# design.net
KiCad netlist of a schematic drawn in Altium Designer
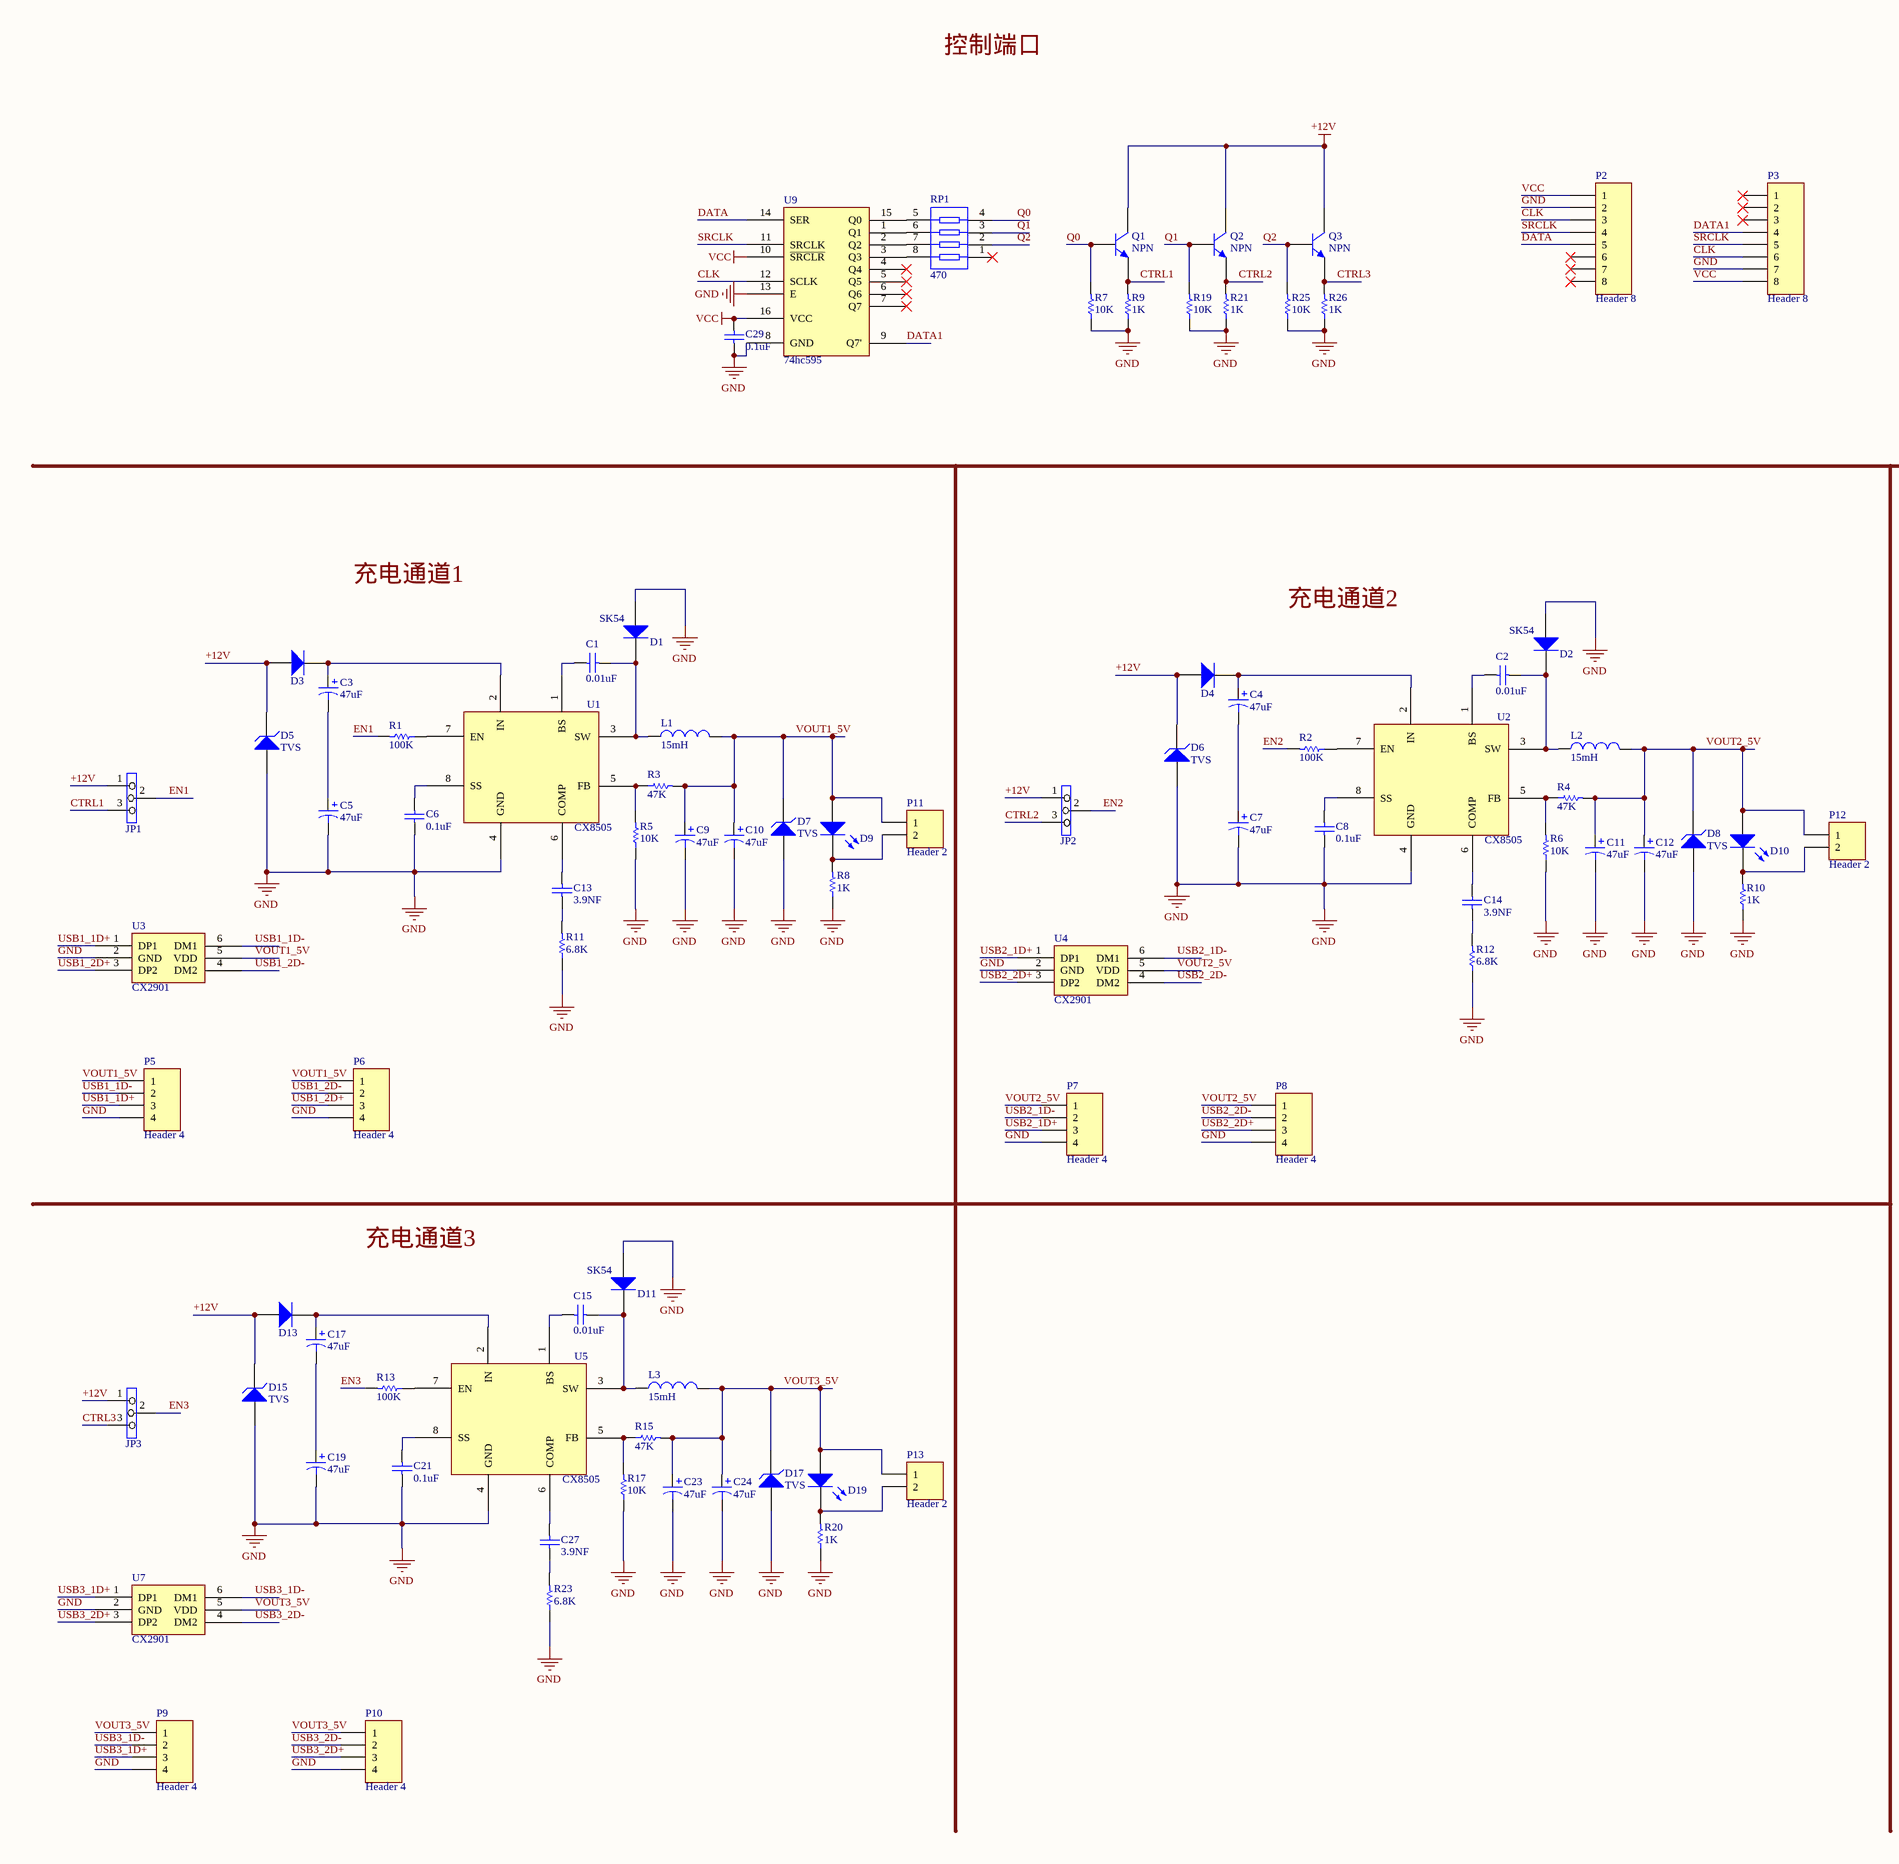
[diagram p0: 充电.SchDoc, left]
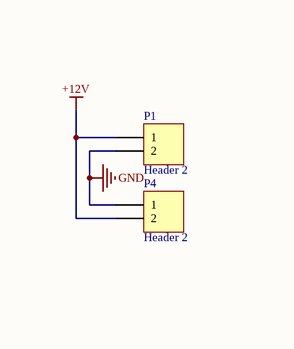
[diagram p1: 充电.SchDoc, right]

(export (version "E")
  (design (tool "Eeschema 10.0.6"))
  (components
    (comp (ref "C1")
      (value "0.01uF")
      (footprint "CAPC2012M")
      (description "Capacitor")
      (fields (field (name "PUBLISHER") "Altium Limited"))
      (libsource (lib "device") (part "Cap"))
    )
    (comp (ref "C2")
      (value "0.01uF")
      (footprint "CAPC2012M")
      (description "Capacitor")
      (fields (field (name "PUBLISHER") "Altium Limited"))
      (libsource (lib "device") (part "Cap"))
    )
    (comp (ref "C3")
      (value "47uF")
      (footprint "CAPPR2-5x11.5")
      (description "Polarized Capacitor (22uf-47uf)")
      (fields (field (name "PUBLISHER") "Altium Limited"))
      (libsource (lib "device") (part "Cap Pol2"))
    )
    (comp (ref "C4")
      (value "47uF")
      (footprint "CAPPR2-5x11.5")
      (description "Polarized Capacitor (22uf-47uf)")
      (fields (field (name "PUBLISHER") "Altium Limited"))
      (libsource (lib "device") (part "Cap Pol2"))
    )
    (comp (ref "C5")
      (value "47uF")
      (footprint "CAPPR2-5x11.5")
      (description "Polarized Capacitor (22uf-47uf)")
      (fields (field (name "PUBLISHER") "Altium Limited"))
      (libsource (lib "device") (part "Cap Pol2"))
    )
    (comp (ref "C6")
      (value "0.1uF")
      (footprint "CAPC2012M")
      (description "Capacitor")
      (fields (field (name "PUBLISHER") "Altium Limited"))
      (libsource (lib "device") (part "Cap"))
    )
    (comp (ref "C7")
      (value "47uF")
      (footprint "CAPPR2-5x11.5")
      (description "Polarized Capacitor (22uf-47uf)")
      (fields (field (name "PUBLISHER") "Altium Limited"))
      (libsource (lib "device") (part "Cap Pol2"))
    )
    (comp (ref "C8")
      (value "0.1uF")
      (footprint "CAPC2012M")
      (description "Capacitor")
      (fields (field (name "PUBLISHER") "Altium Limited"))
      (libsource (lib "device") (part "Cap"))
    )
    (comp (ref "C9")
      (value "47uF")
      (footprint "CAPPR2-5x11.5")
      (description "Polarized Capacitor (22uf-47uf)")
      (fields (field (name "PUBLISHER") "Altium Limited"))
      (libsource (lib "device") (part "Cap Pol2"))
    )
    (comp (ref "C10")
      (value "47uF")
      (footprint "CAPPR2-5x11.5")
      (description "Polarized Capacitor (22uf-47uf)")
      (fields (field (name "PUBLISHER") "Altium Limited"))
      (libsource (lib "device") (part "Cap Pol2"))
    )
    (comp (ref "C11")
      (value "47uF")
      (footprint "CAPPR2-5x11.5")
      (description "Polarized Capacitor (22uf-47uf)")
      (fields (field (name "PUBLISHER") "Altium Limited"))
      (libsource (lib "device") (part "Cap Pol2"))
    )
    (comp (ref "C12")
      (value "47uF")
      (footprint "CAPPR2-5x11.5")
      (description "Polarized Capacitor (22uf-47uf)")
      (fields (field (name "PUBLISHER") "Altium Limited"))
      (libsource (lib "device") (part "Cap Pol2"))
    )
    (comp (ref "C13")
      (value "3.9NF")
      (footprint "CAPC2012M")
      (description "Capacitor")
      (fields (field (name "PUBLISHER") "Altium Limited"))
      (libsource (lib "device") (part "Cap"))
    )
    (comp (ref "C14")
      (value "3.9NF")
      (footprint "CAPC2012M")
      (description "Capacitor")
      (fields (field (name "PUBLISHER") "Altium Limited"))
      (libsource (lib "device") (part "Cap"))
    )
    (comp (ref "C15")
      (value "0.01uF")
      (footprint "CAPC2012M")
      (description "Capacitor")
      (fields (field (name "PUBLISHER") "Altium Limited"))
      (libsource (lib "device") (part "Cap"))
    )
    (comp (ref "C17")
      (value "47uF")
      (footprint "CAPPR2-5x11.5")
      (description "Polarized Capacitor (22uf-47uf)")
      (fields (field (name "PUBLISHER") "Altium Limited"))
      (libsource (lib "device") (part "Cap Pol2"))
    )
    (comp (ref "C19")
      (value "47uF")
      (footprint "CAPPR2-5x11.5")
      (description "Polarized Capacitor (22uf-47uf)")
      (fields (field (name "PUBLISHER") "Altium Limited"))
      (libsource (lib "device") (part "Cap Pol2"))
    )
    (comp (ref "C21")
      (value "0.1uF")
      (footprint "CAPC2012M")
      (description "Capacitor")
      (fields (field (name "PUBLISHER") "Altium Limited"))
      (libsource (lib "device") (part "Cap"))
    )
    (comp (ref "C23")
      (value "47uF")
      (footprint "CAPPR2-5x11.5")
      (description "Polarized Capacitor (22uf-47uf)")
      (fields (field (name "PUBLISHER") "Altium Limited"))
      (libsource (lib "device") (part "Cap Pol2"))
    )
    (comp (ref "C24")
      (value "47uF")
      (footprint "CAPPR2-5x11.5")
      (description "Polarized Capacitor (22uf-47uf)")
      (fields (field (name "PUBLISHER") "Altium Limited"))
      (libsource (lib "device") (part "Cap Pol2"))
    )
    (comp (ref "C27")
      (value "3.9NF")
      (footprint "CAPC2012M")
      (description "Capacitor")
      (fields (field (name "PUBLISHER") "Altium Limited"))
      (libsource (lib "device") (part "Cap"))
    )
    (comp (ref "C29")
      (value "0.1uF")
      (footprint "CAPC2012M")
      (description "Capacitor")
      (fields (field (name "PUBLISHER") "Altium Limited"))
      (libsource (lib "device") (part "Cap"))
    )
    (comp (ref "D1")
      (value "SK54")
      (footprint "SMC")
      (description "Default Diode")
      (fields (field (name "PUBLISHER") "Altium Limited"))
      (libsource (lib "") (part "Diode_1"))
    )
    (comp (ref "D2")
      (value "SK54")
      (footprint "SMC")
      (description "Default Diode")
      (fields (field (name "PUBLISHER") "Altium Limited"))
      (libsource (lib "") (part "Diode_1"))
    )
    (comp (ref "D3")
      (value "1N4007")
      (footprint "DSO-C2/X1.8")
      (description "Default Diode")
      (fields (field (name "PUBLISHER") "Altium Limited"))
      (libsource (lib "device") (part "Diode"))
    )
    (comp (ref "D4")
      (value "1N4007")
      (footprint "DSO-C2/X1.8")
      (description "Default Diode")
      (fields (field (name "PUBLISHER") "Altium Limited"))
      (libsource (lib "device") (part "Diode"))
    )
    (comp (ref "D5")
      (value "TVS")
      (footprint "SMB")
      (description "TVS瞬态抑制二极管")
      (fields (field (name "PUBLISHER") "Altium Limited"))
      (libsource (lib "device") (part "TVS"))
    )
    (comp (ref "D6")
      (value "TVS")
      (footprint "SMB")
      (description "TVS瞬态抑制二极管")
      (fields (field (name "PUBLISHER") "Altium Limited"))
      (libsource (lib "device") (part "TVS"))
    )
    (comp (ref "D7")
      (value "TVS")
      (footprint "DSO-C2/X1.8")
      (description "TVS瞬态抑制二极管")
      (fields (field (name "PUBLISHER") "Altium Limited"))
      (libsource (lib "device") (part "TVS"))
    )
    (comp (ref "D8")
      (value "TVS")
      (footprint "DSO-C2/X1.8")
      (description "TVS瞬态抑制二极管")
      (fields (field (name "PUBLISHER") "Altium Limited"))
      (libsource (lib "device") (part "TVS"))
    )
    (comp (ref "D9")
      (value "LED")
      (footprint "LED")
      (description "Typical INFRARED GaAs LED")
      (fields (field (name "PUBLISHER") "Altium Limited"))
      (libsource (lib "device") (part "LED"))
    )
    (comp (ref "D10")
      (value "LED")
      (footprint "LED")
      (description "Typical INFRARED GaAs LED")
      (fields (field (name "PUBLISHER") "Altium Limited"))
      (libsource (lib "device") (part "LED"))
    )
    (comp (ref "D11")
      (value "SK54")
      (footprint "SMC")
      (description "Default Diode")
      (fields (field (name "PUBLISHER") "Altium Limited"))
      (libsource (lib "") (part "Diode_1"))
    )
    (comp (ref "D13")
      (value "1N4007")
      (footprint "DSO-C2/X1.8")
      (description "Default Diode")
      (fields (field (name "PUBLISHER") "Altium Limited"))
      (libsource (lib "device") (part "Diode"))
    )
    (comp (ref "D15")
      (value "TVS")
      (footprint "SMB")
      (description "TVS瞬态抑制二极管")
      (fields (field (name "PUBLISHER") "Altium Limited"))
      (libsource (lib "device") (part "TVS"))
    )
    (comp (ref "D17")
      (value "TVS")
      (footprint "DSO-C2/X1.8")
      (description "TVS瞬态抑制二极管")
      (fields (field (name "PUBLISHER") "Altium Limited"))
      (libsource (lib "device") (part "TVS"))
    )
    (comp (ref "D19")
      (value "LED")
      (footprint "LED")
      (description "Typical INFRARED GaAs LED")
      (fields (field (name "PUBLISHER") "Altium Limited"))
      (libsource (lib "device") (part "LED"))
    )
    (comp (ref "JP1") (value "Jumper3") (footprint "JP3") (libsource (lib "connector") (part "Jumper3")))
    (comp (ref "JP2") (value "Jumper3") (footprint "JP3") (libsource (lib "connector") (part "Jumper3")))
    (comp (ref "JP3") (value "Jumper3") (footprint "JP3") (libsource (lib "connector") (part "Jumper3")))
    (comp (ref "L1")
      (value "15mH")
      (footprint "15mh电感")
      (description "Inductor")
      (fields (field (name "PUBLISHER") "Altium Limited"))
      (libsource (lib "device") (part "Inductor"))
    )
    (comp (ref "L2")
      (value "15mH")
      (footprint "15mh电感")
      (description "Inductor")
      (fields (field (name "PUBLISHER") "Altium Limited"))
      (libsource (lib "device") (part "Inductor"))
    )
    (comp (ref "L3")
      (value "15mH")
      (footprint "15mh电感")
      (description "Inductor")
      (fields (field (name "PUBLISHER") "Altium Limited"))
      (libsource (lib "device") (part "Inductor"))
    )
    (comp (ref "P1")
      (value "Header 2")
      (footprint "VH396-2")
      (description "Header, 2-Pin")
      (fields (field (name "PUBLISHER") "Altium Limited"))
      (libsource (lib "connector") (part "Header 2"))
    )
    (comp (ref "P2")
      (value "Header 8")
      (footprint "XH254-8")
      (description "Header, 8-Pin")
      (fields (field (name "PUBLISHER") "Altium Limited"))
      (libsource (lib "connector") (part "Header 8"))
    )
    (comp (ref "P3")
      (value "Header 8")
      (footprint "XH254-8")
      (description "Header, 8-Pin")
      (fields (field (name "PUBLISHER") "Altium Limited"))
      (libsource (lib "connector") (part "Header 8"))
    )
    (comp (ref "P4")
      (value "Header 2")
      (footprint "VH396-2")
      (description "Header, 2-Pin")
      (fields (field (name "PUBLISHER") "Altium Limited"))
      (libsource (lib "connector") (part "Header 2"))
    )
    (comp (ref "P5")
      (value "Header 4")
      (footprint "XH254-4")
      (description "Header, 4-Pin")
      (fields (field (name "PUBLISHER") "Altium Limited"))
      (libsource (lib "connector") (part "Header 4"))
    )
    (comp (ref "P6")
      (value "Header 4")
      (footprint "XH254-4")
      (description "Header, 4-Pin")
      (fields (field (name "PUBLISHER") "Altium Limited"))
      (libsource (lib "connector") (part "Header 4"))
    )
    (comp (ref "P7")
      (value "Header 4")
      (footprint "XH254-4")
      (description "Header, 4-Pin")
      (fields (field (name "PUBLISHER") "Altium Limited"))
      (libsource (lib "connector") (part "Header 4"))
    )
    (comp (ref "P8")
      (value "Header 4")
      (footprint "XH254-4")
      (description "Header, 4-Pin")
      (fields (field (name "PUBLISHER") "Altium Limited"))
      (libsource (lib "connector") (part "Header 4"))
    )
    (comp (ref "P9")
      (value "Header 4")
      (footprint "XH254-4")
      (description "Header, 4-Pin")
      (fields (field (name "PUBLISHER") "Altium Limited"))
      (libsource (lib "connector") (part "Header 4"))
    )
    (comp (ref "P10")
      (value "Header 4")
      (footprint "XH254-4")
      (description "Header, 4-Pin")
      (fields (field (name "PUBLISHER") "Altium Limited"))
      (libsource (lib "connector") (part "Header 4"))
    )
    (comp (ref "P11")
      (value "Header 2")
      (footprint "XH254-2")
      (description "Header, 2-Pin")
      (fields (field (name "PUBLISHER") "Altium Limited"))
      (libsource (lib "connector") (part "Header 2"))
    )
    (comp (ref "P12")
      (value "Header 2")
      (footprint "XH254-2")
      (description "Header, 2-Pin")
      (fields (field (name "PUBLISHER") "Altium Limited"))
      (libsource (lib "connector") (part "Header 2"))
    )
    (comp (ref "P13")
      (value "Header 2")
      (footprint "XH254-2")
      (description "Header, 2-Pin")
      (fields (field (name "PUBLISHER") "Altium Limited"))
      (libsource (lib "connector") (part "Header 2"))
    )
    (comp (ref "Q1")
      (value "NPN")
      (footprint "SOT23-3M")
      (description "NPN Bipolar Transistor")
      (fields (field (name "PUBLISHER") "Altium Limited"))
      (libsource (lib "device") (part "NPN"))
    )
    (comp (ref "Q2")
      (value "NPN")
      (footprint "SOT23-3M")
      (description "NPN Bipolar Transistor")
      (fields (field (name "PUBLISHER") "Altium Limited"))
      (libsource (lib "device") (part "NPN"))
    )
    (comp (ref "Q3")
      (value "NPN")
      (footprint "SOT23-3M")
      (description "NPN Bipolar Transistor")
      (fields (field (name "PUBLISHER") "Altium Limited"))
      (libsource (lib "device") (part "NPN"))
    )
    (comp (ref "R1")
      (value "100K")
      (footprint "RESC2012M")
      (description "Resistor")
      (fields (field (name "PUBLISHER") "Altium Limited"))
      (libsource (lib "device") (part "Res"))
    )
    (comp (ref "R2")
      (value "100K")
      (footprint "RESC2012M")
      (description "Resistor")
      (fields (field (name "PUBLISHER") "Altium Limited"))
      (libsource (lib "device") (part "Res"))
    )
    (comp (ref "R3")
      (value "47K")
      (footprint "RESC2012M")
      (description "Resistor")
      (fields (field (name "PUBLISHER") "Altium Limited"))
      (libsource (lib "device") (part "Res"))
    )
    (comp (ref "R4")
      (value "47K")
      (footprint "RESC2012M")
      (description "Resistor")
      (fields (field (name "PUBLISHER") "Altium Limited"))
      (libsource (lib "device") (part "Res"))
    )
    (comp (ref "R5")
      (value "10K")
      (footprint "RESC2012M")
      (description "Resistor")
      (fields (field (name "PUBLISHER") "Altium Limited"))
      (libsource (lib "device") (part "Res"))
    )
    (comp (ref "R6")
      (value "10K")
      (footprint "RESC2012M")
      (description "Resistor")
      (fields (field (name "PUBLISHER") "Altium Limited"))
      (libsource (lib "device") (part "Res"))
    )
    (comp (ref "R7")
      (value "10K")
      (footprint "RESC2012M")
      (description "Resistor")
      (fields (field (name "PUBLISHER") "Altium Limited"))
      (libsource (lib "device") (part "Res"))
    )
    (comp (ref "R8")
      (value "1K")
      (footprint "RESC2012M")
      (description "Resistor")
      (fields (field (name "PUBLISHER") "Altium Limited"))
      (libsource (lib "device") (part "Res"))
    )
    (comp (ref "R9")
      (value "1K")
      (footprint "RESC2012M")
      (description "Resistor")
      (fields (field (name "PUBLISHER") "Altium Limited"))
      (libsource (lib "device") (part "Res"))
    )
    (comp (ref "R10")
      (value "1K")
      (footprint "RESC2012M")
      (description "Resistor")
      (fields (field (name "PUBLISHER") "Altium Limited"))
      (libsource (lib "device") (part "Res"))
    )
    (comp (ref "R11")
      (value "6.8K")
      (footprint "RESC2012M")
      (description "Resistor")
      (fields (field (name "PUBLISHER") "Altium Limited"))
      (libsource (lib "device") (part "Res"))
    )
    (comp (ref "R12")
      (value "6.8K")
      (footprint "RESC2012M")
      (description "Resistor")
      (fields (field (name "PUBLISHER") "Altium Limited"))
      (libsource (lib "device") (part "Res"))
    )
    (comp (ref "R13")
      (value "100K")
      (footprint "RESC2012M")
      (description "Resistor")
      (fields (field (name "PUBLISHER") "Altium Limited"))
      (libsource (lib "device") (part "Res"))
    )
    (comp (ref "R15")
      (value "47K")
      (footprint "RESC2012M")
      (description "Resistor")
      (fields (field (name "PUBLISHER") "Altium Limited"))
      (libsource (lib "device") (part "Res"))
    )
    (comp (ref "R17")
      (value "10K")
      (footprint "RESC2012M")
      (description "Resistor")
      (fields (field (name "PUBLISHER") "Altium Limited"))
      (libsource (lib "device") (part "Res"))
    )
    (comp (ref "R19")
      (value "10K")
      (footprint "RESC2012M")
      (description "Resistor")
      (fields (field (name "PUBLISHER") "Altium Limited"))
      (libsource (lib "device") (part "Res"))
    )
    (comp (ref "R20")
      (value "1K")
      (footprint "RESC2012M")
      (description "Resistor")
      (fields (field (name "PUBLISHER") "Altium Limited"))
      (libsource (lib "device") (part "Res"))
    )
    (comp (ref "R21")
      (value "1K")
      (footprint "RESC2012M")
      (description "Resistor")
      (fields (field (name "PUBLISHER") "Altium Limited"))
      (libsource (lib "device") (part "Res"))
    )
    (comp (ref "R23")
      (value "6.8K")
      (footprint "RESC2012M")
      (description "Resistor")
      (fields (field (name "PUBLISHER") "Altium Limited"))
      (libsource (lib "device") (part "Res"))
    )
    (comp (ref "R25")
      (value "10K")
      (footprint "RESC2012M")
      (description "Resistor")
      (fields (field (name "PUBLISHER") "Altium Limited"))
      (libsource (lib "device") (part "Res"))
    )
    (comp (ref "R26")
      (value "1K")
      (footprint "RESC2012M")
      (description "Resistor")
      (fields (field (name "PUBLISHER") "Altium Limited"))
      (libsource (lib "device") (part "Res"))
    )
    (comp (ref "RP1") (value "470") (footprint "EXB38V") (libsource (lib "device") (part "Res Pack")))
    (comp (ref "U1") (value "CX8505") (footprint "SO8_M") (libsource (lib "ic") (part "CX8505")))
    (comp (ref "U2") (value "CX8505") (footprint "SO8_M") (libsource (lib "ic") (part "CX8505")))
    (comp (ref "U3") (value "CX2901") (footprint "SOT23_6L") (libsource (lib "ic") (part "CX2901")))
    (comp (ref "U4") (value "CX2901") (footprint "SOT23_6L") (libsource (lib "ic") (part "CX2901")))
    (comp (ref "U5") (value "CX8505") (footprint "SO8_M") (libsource (lib "ic") (part "CX8505")))
    (comp (ref "U7") (value "CX2901") (footprint "SOT23_6L") (libsource (lib "ic") (part "CX2901")))
    (comp (ref "U9") (value "74hc595") (footprint "SO16_M") (libsource (lib "ic") (part "74hc595")))
  )
  (nets
    (net (code "1") (name "+12V") (class "Default")
      (node (ref "D13") (pin "1") (pinfunction "A_1") (pintype "passive"))
      (node (ref "D15") (pin "2") (pinfunction "K_2") (pintype "passive"))
      (node (ref "D3") (pin "1") (pinfunction "A_1") (pintype "passive"))
      (node (ref "D4") (pin "1") (pinfunction "A_1") (pintype "passive"))
      (node (ref "D5") (pin "2") (pinfunction "K_2") (pintype "passive"))
      (node (ref "D6") (pin "2") (pinfunction "K_2") (pintype "passive"))
      (node (ref "JP1") (pin "1") (pintype "passive"))
      (node (ref "JP2") (pin "1") (pintype "passive"))
      (node (ref "JP3") (pin "1") (pintype "passive"))
      (node (ref "P1") (pin "1") (pinfunction "1_1") (pintype "passive"))
      (node (ref "P4") (pin "2") (pinfunction "2_2") (pintype "passive"))
      (node (ref "Q1") (pin "3") (pinfunction "C_3") (pintype "passive"))
      (node (ref "Q2") (pin "3") (pinfunction "C_3") (pintype "passive"))
      (node (ref "Q3") (pin "3") (pinfunction "C_3") (pintype "passive"))
    )
    (net (code "2") (name "/CLK") (class "Default")
      (node (ref "P2") (pin "3") (pinfunction "3_3") (pintype "passive"))
      (node (ref "P3") (pin "6") (pinfunction "6_6") (pintype "passive"))
      (node (ref "U9") (pin "12") (pinfunction "SCLK_12") (pintype "passive"))
    )
    (net (code "3") (name "/CTRL1") (class "Default")
      (node (ref "JP1") (pin "3") (pintype "passive"))
      (node (ref "Q1") (pin "2") (pinfunction "E_2") (pintype "passive"))
      (node (ref "R9") (pin "2") (pinfunction "2_2") (pintype "passive"))
    )
    (net (code "4") (name "/CTRL2") (class "Default")
      (node (ref "JP2") (pin "3") (pintype "passive"))
      (node (ref "Q2") (pin "2") (pinfunction "E_2") (pintype "passive"))
      (node (ref "R21") (pin "2") (pinfunction "2_2") (pintype "passive"))
    )
    (net (code "5") (name "/CTRL3") (class "Default")
      (node (ref "JP3") (pin "3") (pintype "passive"))
      (node (ref "Q3") (pin "2") (pinfunction "E_2") (pintype "passive"))
      (node (ref "R26") (pin "2") (pinfunction "2_2") (pintype "passive"))
    )
    (net (code "6") (name "/DATA") (class "Default")
      (node (ref "P2") (pin "5") (pinfunction "5_5") (pintype "passive"))
      (node (ref "U9") (pin "14") (pinfunction "SER_14") (pintype "passive"))
    )
    (net (code "7") (name "/DATA1") (class "Default")
      (node (ref "P3") (pin "4") (pinfunction "4_4") (pintype "passive"))
      (node (ref "U9") (pin "9") (pinfunction "Q7'_9") (pintype "passive"))
    )
    (net (code "8") (name "/EN1") (class "Default")
      (node (ref "JP1") (pin "2") (pintype "passive"))
      (node (ref "R1") (pin "2") (pinfunction "2_2") (pintype "passive"))
    )
    (net (code "9") (name "/EN2") (class "Default")
      (node (ref "JP2") (pin "2") (pintype "passive"))
      (node (ref "R2") (pin "2") (pinfunction "2_2") (pintype "passive"))
    )
    (net (code "10") (name "/EN3") (class "Default")
      (node (ref "JP3") (pin "2") (pintype "passive"))
      (node (ref "R13") (pin "2") (pinfunction "2_2") (pintype "passive"))
    )
    (net (code "11") (name "/Q0") (class "Default")
      (node (ref "Q1") (pin "1") (pinfunction "B_1") (pintype "passive"))
      (node (ref "R7") (pin "2") (pinfunction "2_2") (pintype "passive"))
      (node (ref "RP1") (pin "4") (pinfunction "4_4") (pintype "passive"))
    )
    (net (code "12") (name "/Q1") (class "Default")
      (node (ref "Q2") (pin "1") (pinfunction "B_1") (pintype "passive"))
      (node (ref "R19") (pin "2") (pinfunction "2_2") (pintype "passive"))
      (node (ref "RP1") (pin "3") (pinfunction "3_3") (pintype "passive"))
    )
    (net (code "13") (name "/Q2") (class "Default")
      (node (ref "Q3") (pin "1") (pinfunction "B_1") (pintype "passive"))
      (node (ref "R25") (pin "2") (pinfunction "2_2") (pintype "passive"))
      (node (ref "RP1") (pin "2") (pinfunction "2_2") (pintype "passive"))
    )
    (net (code "14") (name "/SRCLK") (class "Default")
      (node (ref "P2") (pin "4") (pinfunction "4_4") (pintype "passive"))
      (node (ref "P3") (pin "5") (pinfunction "5_5") (pintype "passive"))
      (node (ref "U9") (pin "11") (pinfunction "SRCLK_11") (pintype "passive"))
    )
    (net (code "15") (name "/USB1_1D+") (class "Default")
      (node (ref "P5") (pin "3") (pinfunction "3_3") (pintype "passive"))
      (node (ref "U3") (pin "1") (pinfunction "DP1_1") (pintype "passive"))
    )
    (net (code "16") (name "/USB1_1D-") (class "Default")
      (node (ref "P5") (pin "2") (pinfunction "2_2") (pintype "passive"))
      (node (ref "U3") (pin "6") (pinfunction "DM1_6") (pintype "passive"))
    )
    (net (code "17") (name "/USB1_2D+") (class "Default")
      (node (ref "P6") (pin "3") (pinfunction "3_3") (pintype "passive"))
      (node (ref "U3") (pin "3") (pinfunction "DP2_3") (pintype "passive"))
    )
    (net (code "18") (name "/USB1_2D-") (class "Default")
      (node (ref "P6") (pin "2") (pinfunction "2_2") (pintype "passive"))
      (node (ref "U3") (pin "4") (pinfunction "DM2_4") (pintype "passive"))
    )
    (net (code "19") (name "/USB2_1D+") (class "Default")
      (node (ref "P7") (pin "3") (pinfunction "3_3") (pintype "passive"))
      (node (ref "U4") (pin "1") (pinfunction "DP1_1") (pintype "passive"))
    )
    (net (code "20") (name "/USB2_1D-") (class "Default")
      (node (ref "P7") (pin "2") (pinfunction "2_2") (pintype "passive"))
      (node (ref "U4") (pin "6") (pinfunction "DM1_6") (pintype "passive"))
    )
    (net (code "21") (name "/USB2_2D+") (class "Default")
      (node (ref "P8") (pin "3") (pinfunction "3_3") (pintype "passive"))
      (node (ref "U4") (pin "3") (pinfunction "DP2_3") (pintype "passive"))
    )
    (net (code "22") (name "/USB2_2D-") (class "Default")
      (node (ref "P8") (pin "2") (pinfunction "2_2") (pintype "passive"))
      (node (ref "U4") (pin "4") (pinfunction "DM2_4") (pintype "passive"))
    )
    (net (code "23") (name "/USB3_1D+") (class "Default")
      (node (ref "P9") (pin "3") (pinfunction "3_3") (pintype "passive"))
      (node (ref "U7") (pin "1") (pinfunction "DP1_1") (pintype "passive"))
    )
    (net (code "24") (name "/USB3_1D-") (class "Default")
      (node (ref "P9") (pin "2") (pinfunction "2_2") (pintype "passive"))
      (node (ref "U7") (pin "6") (pinfunction "DM1_6") (pintype "passive"))
    )
    (net (code "25") (name "/USB3_2D+") (class "Default")
      (node (ref "P10") (pin "3") (pinfunction "3_3") (pintype "passive"))
      (node (ref "U7") (pin "3") (pinfunction "DP2_3") (pintype "passive"))
    )
    (net (code "26") (name "/USB3_2D-") (class "Default")
      (node (ref "P10") (pin "2") (pinfunction "2_2") (pintype "passive"))
      (node (ref "U7") (pin "4") (pinfunction "DM2_4") (pintype "passive"))
    )
    (net (code "27") (name "/VOUT1_5V") (class "Default")
      (node (ref "C10") (pin "1") (pinfunction "1_1") (pintype "passive"))
      (node (ref "C9") (pin "1") (pinfunction "1_1") (pintype "passive"))
      (node (ref "D7") (pin "2") (pinfunction "K_2") (pintype "passive"))
      (node (ref "D9") (pin "1") (pinfunction "A_1") (pintype "passive"))
      (node (ref "L1") (pin "2") (pinfunction "2_2") (pintype "passive"))
      (node (ref "P11") (pin "1") (pinfunction "1_1") (pintype "passive"))
      (node (ref "P5") (pin "1") (pinfunction "1_1") (pintype "passive"))
      (node (ref "P6") (pin "1") (pinfunction "1_1") (pintype "passive"))
      (node (ref "R3") (pin "2") (pinfunction "2_2") (pintype "passive"))
      (node (ref "U3") (pin "5") (pinfunction "VDD_5") (pintype "passive"))
    )
    (net (code "28") (name "/VOUT2_5V") (class "Default")
      (node (ref "C11") (pin "1") (pinfunction "1_1") (pintype "passive"))
      (node (ref "C12") (pin "1") (pinfunction "1_1") (pintype "passive"))
      (node (ref "D10") (pin "1") (pinfunction "A_1") (pintype "passive"))
      (node (ref "D8") (pin "2") (pinfunction "K_2") (pintype "passive"))
      (node (ref "L2") (pin "2") (pinfunction "2_2") (pintype "passive"))
      (node (ref "P12") (pin "1") (pinfunction "1_1") (pintype "passive"))
      (node (ref "P7") (pin "1") (pinfunction "1_1") (pintype "passive"))
      (node (ref "P8") (pin "1") (pinfunction "1_1") (pintype "passive"))
      (node (ref "R4") (pin "2") (pinfunction "2_2") (pintype "passive"))
      (node (ref "U4") (pin "5") (pinfunction "VDD_5") (pintype "passive"))
    )
    (net (code "29") (name "/VOUT3_5V") (class "Default")
      (node (ref "C23") (pin "1") (pinfunction "1_1") (pintype "passive"))
      (node (ref "C24") (pin "1") (pinfunction "1_1") (pintype "passive"))
      (node (ref "D17") (pin "2") (pinfunction "K_2") (pintype "passive"))
      (node (ref "D19") (pin "1") (pinfunction "A_1") (pintype "passive"))
      (node (ref "L3") (pin "2") (pinfunction "2_2") (pintype "passive"))
      (node (ref "P10") (pin "1") (pinfunction "1_1") (pintype "passive"))
      (node (ref "P13") (pin "1") (pinfunction "1_1") (pintype "passive"))
      (node (ref "P9") (pin "1") (pinfunction "1_1") (pintype "passive"))
      (node (ref "R15") (pin "2") (pinfunction "2_2") (pintype "passive"))
      (node (ref "U7") (pin "5") (pinfunction "VDD_5") (pintype "passive"))
    )
    (net (code "30") (name "GND") (class "Default")
      (node (ref "C10") (pin "2") (pinfunction "2_2") (pintype "passive"))
      (node (ref "C11") (pin "2") (pinfunction "2_2") (pintype "passive"))
      (node (ref "C12") (pin "2") (pinfunction "2_2") (pintype "passive"))
      (node (ref "C19") (pin "2") (pinfunction "2_2") (pintype "passive"))
      (node (ref "C21") (pin "1") (pinfunction "1_1") (pintype "passive"))
      (node (ref "C23") (pin "2") (pinfunction "2_2") (pintype "passive"))
      (node (ref "C24") (pin "2") (pinfunction "2_2") (pintype "passive"))
      (node (ref "C29") (pin "1") (pinfunction "1_1") (pintype "passive"))
      (node (ref "C5") (pin "2") (pinfunction "2_2") (pintype "passive"))
      (node (ref "C6") (pin "1") (pinfunction "1_1") (pintype "passive"))
      (node (ref "C7") (pin "2") (pinfunction "2_2") (pintype "passive"))
      (node (ref "C8") (pin "1") (pinfunction "1_1") (pintype "passive"))
      (node (ref "C9") (pin "2") (pinfunction "2_2") (pintype "passive"))
      (node (ref "D1") (pin "2") (pinfunction "A_2") (pintype "passive"))
      (node (ref "D11") (pin "2") (pinfunction "A_2") (pintype "passive"))
      (node (ref "D15") (pin "1") (pinfunction "A_1") (pintype "passive"))
      (node (ref "D17") (pin "1") (pinfunction "A_1") (pintype "passive"))
      (node (ref "D2") (pin "2") (pinfunction "A_2") (pintype "passive"))
      (node (ref "D5") (pin "1") (pinfunction "A_1") (pintype "passive"))
      (node (ref "D6") (pin "1") (pinfunction "A_1") (pintype "passive"))
      (node (ref "D7") (pin "1") (pinfunction "A_1") (pintype "passive"))
      (node (ref "D8") (pin "1") (pinfunction "A_1") (pintype "passive"))
      (node (ref "P1") (pin "2") (pinfunction "2_2") (pintype "passive"))
      (node (ref "P10") (pin "4") (pinfunction "4_4") (pintype "passive"))
      (node (ref "P2") (pin "2") (pinfunction "2_2") (pintype "passive"))
      (node (ref "P3") (pin "7") (pinfunction "7_7") (pintype "passive"))
      (node (ref "P4") (pin "1") (pinfunction "1_1") (pintype "passive"))
      (node (ref "P5") (pin "4") (pinfunction "4_4") (pintype "passive"))
      (node (ref "P6") (pin "4") (pinfunction "4_4") (pintype "passive"))
      (node (ref "P7") (pin "4") (pinfunction "4_4") (pintype "passive"))
      (node (ref "P8") (pin "4") (pinfunction "4_4") (pintype "passive"))
      (node (ref "P9") (pin "4") (pinfunction "4_4") (pintype "passive"))
      (node (ref "R10") (pin "1") (pinfunction "1_1") (pintype "passive"))
      (node (ref "R11") (pin "1") (pinfunction "1_1") (pintype "passive"))
      (node (ref "R12") (pin "1") (pinfunction "1_1") (pintype "passive"))
      (node (ref "R17") (pin "1") (pinfunction "1_1") (pintype "passive"))
      (node (ref "R19") (pin "1") (pinfunction "1_1") (pintype "passive"))
      (node (ref "R20") (pin "1") (pinfunction "1_1") (pintype "passive"))
      (node (ref "R21") (pin "1") (pinfunction "1_1") (pintype "passive"))
      (node (ref "R23") (pin "1") (pinfunction "1_1") (pintype "passive"))
      (node (ref "R25") (pin "1") (pinfunction "1_1") (pintype "passive"))
      (node (ref "R26") (pin "1") (pinfunction "1_1") (pintype "passive"))
      (node (ref "R5") (pin "1") (pinfunction "1_1") (pintype "passive"))
      (node (ref "R6") (pin "1") (pinfunction "1_1") (pintype "passive"))
      (node (ref "R7") (pin "1") (pinfunction "1_1") (pintype "passive"))
      (node (ref "R8") (pin "1") (pinfunction "1_1") (pintype "passive"))
      (node (ref "R9") (pin "1") (pinfunction "1_1") (pintype "passive"))
      (node (ref "U1") (pin "4") (pinfunction "GND_4") (pintype "passive"))
      (node (ref "U2") (pin "4") (pinfunction "GND_4") (pintype "passive"))
      (node (ref "U3") (pin "2") (pinfunction "GND_2") (pintype "passive"))
      (node (ref "U4") (pin "2") (pinfunction "GND_2") (pintype "passive"))
      (node (ref "U5") (pin "4") (pinfunction "GND_4") (pintype "passive"))
      (node (ref "U7") (pin "2") (pinfunction "GND_2") (pintype "passive"))
      (node (ref "U9") (pin "13") (pinfunction "E_13") (pintype "passive"))
      (node (ref "U9") (pin "8") (pinfunction "GND_8") (pintype "passive"))
    )
    (net (code "31") (name "Net-(C3-Pad2)") (class "Default")
      (node (ref "C3") (pin "2") (pinfunction "2_2") (pintype "passive"))
      (node (ref "C5") (pin "1") (pinfunction "1_1") (pintype "passive"))
    )
    (net (code "32") (name "Net-(C4-Pad2)") (class "Default")
      (node (ref "C4") (pin "2") (pinfunction "2_2") (pintype "passive"))
      (node (ref "C7") (pin "1") (pinfunction "1_1") (pintype "passive"))
    )
    (net (code "33") (name "Net-(C13-Pad1)") (class "Default")
      (node (ref "C13") (pin "1") (pinfunction "1_1") (pintype "passive"))
      (node (ref "R11") (pin "2") (pinfunction "2_2") (pintype "passive"))
    )
    (net (code "34") (name "Net-(C14-Pad1)") (class "Default")
      (node (ref "C14") (pin "1") (pinfunction "1_1") (pintype "passive"))
      (node (ref "R12") (pin "2") (pinfunction "2_2") (pintype "passive"))
    )
    (net (code "35") (name "Net-(C17-Pad2)") (class "Default")
      (node (ref "C17") (pin "2") (pinfunction "2_2") (pintype "passive"))
      (node (ref "C19") (pin "1") (pinfunction "1_1") (pintype "passive"))
    )
    (net (code "36") (name "Net-(C27-Pad1)") (class "Default")
      (node (ref "C27") (pin "1") (pinfunction "1_1") (pintype "passive"))
      (node (ref "R23") (pin "2") (pinfunction "2_2") (pintype "passive"))
    )
    (net (code "37") (name "Net-(D1-K)") (class "Default")
      (node (ref "C1") (pin "1") (pinfunction "1_1") (pintype "passive"))
      (node (ref "D1") (pin "1") (pinfunction "K_1") (pintype "passive"))
      (node (ref "L1") (pin "1") (pinfunction "1_1") (pintype "passive"))
      (node (ref "U1") (pin "3") (pinfunction "SW_3") (pintype "passive"))
    )
    (net (code "38") (name "Net-(D2-K)") (class "Default")
      (node (ref "C2") (pin "1") (pinfunction "1_1") (pintype "passive"))
      (node (ref "D2") (pin "1") (pinfunction "K_1") (pintype "passive"))
      (node (ref "L2") (pin "1") (pinfunction "1_1") (pintype "passive"))
      (node (ref "U2") (pin "3") (pinfunction "SW_3") (pintype "passive"))
    )
    (net (code "39") (name "Net-(D3-K)") (class "Default")
      (node (ref "C3") (pin "1") (pinfunction "1_1") (pintype "passive"))
      (node (ref "D3") (pin "2") (pinfunction "K_2") (pintype "passive"))
      (node (ref "U1") (pin "2") (pinfunction "IN_2") (pintype "passive"))
    )
    (net (code "40") (name "Net-(D4-K)") (class "Default")
      (node (ref "C4") (pin "1") (pinfunction "1_1") (pintype "passive"))
      (node (ref "D4") (pin "2") (pinfunction "K_2") (pintype "passive"))
      (node (ref "U2") (pin "2") (pinfunction "IN_2") (pintype "passive"))
    )
    (net (code "41") (name "Net-(D9-K)") (class "Default")
      (node (ref "D9") (pin "2") (pinfunction "K_2") (pintype "passive"))
      (node (ref "P11") (pin "2") (pinfunction "2_2") (pintype "passive"))
      (node (ref "R8") (pin "2") (pinfunction "2_2") (pintype "passive"))
    )
    (net (code "42") (name "Net-(D10-K)") (class "Default")
      (node (ref "D10") (pin "2") (pinfunction "K_2") (pintype "passive"))
      (node (ref "P12") (pin "2") (pinfunction "2_2") (pintype "passive"))
      (node (ref "R10") (pin "2") (pinfunction "2_2") (pintype "passive"))
    )
    (net (code "43") (name "Net-(D11-K)") (class "Default")
      (node (ref "C15") (pin "1") (pinfunction "1_1") (pintype "passive"))
      (node (ref "D11") (pin "1") (pinfunction "K_1") (pintype "passive"))
      (node (ref "L3") (pin "1") (pinfunction "1_1") (pintype "passive"))
      (node (ref "U5") (pin "3") (pinfunction "SW_3") (pintype "passive"))
    )
    (net (code "44") (name "Net-(D13-K)") (class "Default")
      (node (ref "C17") (pin "1") (pinfunction "1_1") (pintype "passive"))
      (node (ref "D13") (pin "2") (pinfunction "K_2") (pintype "passive"))
      (node (ref "U5") (pin "2") (pinfunction "IN_2") (pintype "passive"))
    )
    (net (code "45") (name "Net-(D19-K)") (class "Default")
      (node (ref "D19") (pin "2") (pinfunction "K_2") (pintype "passive"))
      (node (ref "P13") (pin "2") (pinfunction "2_2") (pintype "passive"))
      (node (ref "R20") (pin "2") (pinfunction "2_2") (pintype "passive"))
    )
    (net (code "46") (name "Net-(U1-BS)") (class "Default")
      (node (ref "C1") (pin "2") (pinfunction "2_2") (pintype "passive"))
      (node (ref "U1") (pin "1") (pinfunction "BS_1") (pintype "passive"))
    )
    (net (code "47") (name "Net-(U1-COMP)") (class "Default")
      (node (ref "C13") (pin "2") (pinfunction "2_2") (pintype "passive"))
      (node (ref "U1") (pin "6") (pinfunction "COMP_6") (pintype "passive"))
    )
    (net (code "48") (name "Net-(U1-EN)") (class "Default")
      (node (ref "R1") (pin "1") (pinfunction "1_1") (pintype "passive"))
      (node (ref "U1") (pin "7") (pinfunction "EN_7") (pintype "passive"))
    )
    (net (code "49") (name "Net-(U1-FB)") (class "Default")
      (node (ref "R3") (pin "1") (pinfunction "1_1") (pintype "passive"))
      (node (ref "R5") (pin "2") (pinfunction "2_2") (pintype "passive"))
      (node (ref "U1") (pin "5") (pinfunction "FB_5") (pintype "passive"))
    )
    (net (code "50") (name "Net-(U1-SS)") (class "Default")
      (node (ref "C6") (pin "2") (pinfunction "2_2") (pintype "passive"))
      (node (ref "U1") (pin "8") (pinfunction "SS_8") (pintype "passive"))
    )
    (net (code "51") (name "Net-(U2-BS)") (class "Default")
      (node (ref "C2") (pin "2") (pinfunction "2_2") (pintype "passive"))
      (node (ref "U2") (pin "1") (pinfunction "BS_1") (pintype "passive"))
    )
    (net (code "52") (name "Net-(U2-COMP)") (class "Default")
      (node (ref "C14") (pin "2") (pinfunction "2_2") (pintype "passive"))
      (node (ref "U2") (pin "6") (pinfunction "COMP_6") (pintype "passive"))
    )
    (net (code "53") (name "Net-(U2-EN)") (class "Default")
      (node (ref "R2") (pin "1") (pinfunction "1_1") (pintype "passive"))
      (node (ref "U2") (pin "7") (pinfunction "EN_7") (pintype "passive"))
    )
    (net (code "54") (name "Net-(U2-FB)") (class "Default")
      (node (ref "R4") (pin "1") (pinfunction "1_1") (pintype "passive"))
      (node (ref "R6") (pin "2") (pinfunction "2_2") (pintype "passive"))
      (node (ref "U2") (pin "5") (pinfunction "FB_5") (pintype "passive"))
    )
    (net (code "55") (name "Net-(U2-SS)") (class "Default")
      (node (ref "C8") (pin "2") (pinfunction "2_2") (pintype "passive"))
      (node (ref "U2") (pin "8") (pinfunction "SS_8") (pintype "passive"))
    )
    (net (code "56") (name "Net-(U5-BS)") (class "Default")
      (node (ref "C15") (pin "2") (pinfunction "2_2") (pintype "passive"))
      (node (ref "U5") (pin "1") (pinfunction "BS_1") (pintype "passive"))
    )
    (net (code "57") (name "Net-(U5-COMP)") (class "Default")
      (node (ref "C27") (pin "2") (pinfunction "2_2") (pintype "passive"))
      (node (ref "U5") (pin "6") (pinfunction "COMP_6") (pintype "passive"))
    )
    (net (code "58") (name "Net-(U5-EN)") (class "Default")
      (node (ref "R13") (pin "1") (pinfunction "1_1") (pintype "passive"))
      (node (ref "U5") (pin "7") (pinfunction "EN_7") (pintype "passive"))
    )
    (net (code "59") (name "Net-(U5-FB)") (class "Default")
      (node (ref "R15") (pin "1") (pinfunction "1_1") (pintype "passive"))
      (node (ref "R17") (pin "2") (pinfunction "2_2") (pintype "passive"))
      (node (ref "U5") (pin "5") (pinfunction "FB_5") (pintype "passive"))
    )
    (net (code "60") (name "Net-(U5-SS)") (class "Default")
      (node (ref "C21") (pin "2") (pinfunction "2_2") (pintype "passive"))
      (node (ref "U5") (pin "8") (pinfunction "SS_8") (pintype "passive"))
    )
    (net (code "61") (name "Net-(U9-Q0)") (class "Default")
      (node (ref "RP1") (pin "5") (pinfunction "5_5") (pintype "passive"))
      (node (ref "U9") (pin "15") (pinfunction "Q0_15") (pintype "passive"))
    )
    (net (code "62") (name "Net-(U9-Q1)") (class "Default")
      (node (ref "RP1") (pin "6") (pinfunction "6_6") (pintype "passive"))
      (node (ref "U9") (pin "1") (pinfunction "Q1_1") (pintype "passive"))
    )
    (net (code "63") (name "Net-(U9-Q2)") (class "Default")
      (node (ref "RP1") (pin "7") (pinfunction "7_7") (pintype "passive"))
      (node (ref "U9") (pin "2") (pinfunction "Q2_2") (pintype "passive"))
    )
    (net (code "64") (name "Net-(U9-Q3)") (class "Default")
      (node (ref "RP1") (pin "8") (pinfunction "8_8") (pintype "passive"))
      (node (ref "U9") (pin "3") (pinfunction "Q3_3") (pintype "passive"))
    )
    (net (code "65") (name "VCC") (class "Default")
      (node (ref "C29") (pin "2") (pinfunction "2_2") (pintype "passive"))
      (node (ref "P2") (pin "1") (pinfunction "1_1") (pintype "passive"))
      (node (ref "P3") (pin "8") (pinfunction "8_8") (pintype "passive"))
      (node (ref "U9") (pin "10") (pinfunction "~{SRCLR}_10") (pintype "passive"))
      (node (ref "U9") (pin "16") (pinfunction "VCC_16") (pintype "passive"))
    )
    (net (code "66") (name "unconnected-(P2-Pad6)") (class "Default")
      (node (ref "P2") (pin "6") (pinfunction "6_6") (pintype "passive+no_connect"))
    )
    (net (code "67") (name "unconnected-(P2-Pad7)") (class "Default")
      (node (ref "P2") (pin "7") (pinfunction "7_7") (pintype "passive+no_connect"))
    )
    (net (code "68") (name "unconnected-(P2-Pad8)") (class "Default")
      (node (ref "P2") (pin "8") (pinfunction "8_8") (pintype "passive+no_connect"))
    )
    (net (code "69") (name "unconnected-(P3-Pad1)") (class "Default")
      (node (ref "P3") (pin "1") (pinfunction "1_1") (pintype "passive+no_connect"))
    )
    (net (code "70") (name "unconnected-(P3-Pad2)") (class "Default")
      (node (ref "P3") (pin "2") (pinfunction "2_2") (pintype "passive+no_connect"))
    )
    (net (code "71") (name "unconnected-(P3-Pad3)") (class "Default")
      (node (ref "P3") (pin "3") (pinfunction "3_3") (pintype "passive+no_connect"))
    )
    (net (code "72") (name "unconnected-(RP1-Pad1)") (class "Default")
      (node (ref "RP1") (pin "1") (pinfunction "1_1") (pintype "passive+no_connect"))
    )
    (net (code "73") (name "unconnected-(U9-Q4-Pad4)") (class "Default")
      (node (ref "U9") (pin "4") (pinfunction "Q4_4") (pintype "passive+no_connect"))
    )
    (net (code "74") (name "unconnected-(U9-Q5-Pad5)") (class "Default")
      (node (ref "U9") (pin "5") (pinfunction "Q5_5") (pintype "passive+no_connect"))
    )
    (net (code "75") (name "unconnected-(U9-Q6-Pad6)") (class "Default")
      (node (ref "U9") (pin "6") (pinfunction "Q6_6") (pintype "passive+no_connect"))
    )
    (net (code "76") (name "unconnected-(U9-Q7-Pad7)") (class "Default")
      (node (ref "U9") (pin "7") (pinfunction "Q7_7") (pintype "passive+no_connect"))
    )
  )
)
